# pong.net
KiCad netlist of a schematic drawn in EAGLE
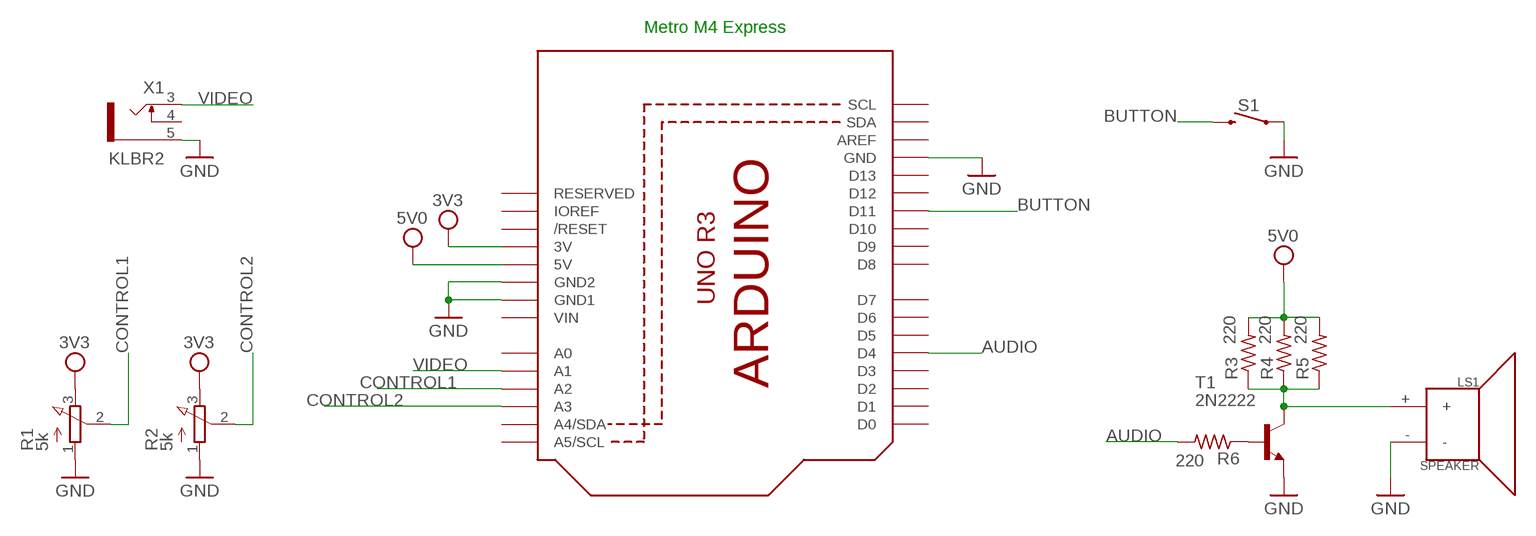
[diagram p0: schematic, sheet 1]

(export (version "E")
  (design (tool "Eeschema 10.0.6"))
  (components
    (comp (ref "LS1")
      (value "SPEAKER")
      (footprint "eagle-import:PCB_MOUNT_SPEAKER")
      (fields (field (name "SPICEPREFIX") "L"))
      (libsource (lib "eagle-import") (part "SPEAKER"))
    )
    (comp (ref "R1")
      (value "5k")
      (footprint "eagle-import:3RP_1610N")
      (libsource (lib "eagle-import") (part "3RP/1610N"))
    )
    (comp (ref "R2")
      (value "5k")
      (footprint "eagle-import:3RP_1610N")
      (libsource (lib "eagle-import") (part "3RP/1610N"))
    )
    (comp (ref "R3")
      (value "220")
      (footprint "eagle-import:0309_12")
      (fields (field (name "SPICEPREFIX") "R"))
      (libsource (lib "eagle-import") (part "R-US_0309/12"))
    )
    (comp (ref "R4")
      (value "220")
      (footprint "eagle-import:0309_12")
      (fields (field (name "SPICEPREFIX") "R"))
      (libsource (lib "eagle-import") (part "R-US_0309/12"))
    )
    (comp (ref "R5")
      (value "220")
      (footprint "eagle-import:0309_12")
      (fields (field (name "SPICEPREFIX") "R"))
      (libsource (lib "eagle-import") (part "R-US_0309/12"))
    )
    (comp (ref "R6")
      (value "220")
      (footprint "eagle-import:0309_12")
      (fields (field (name "SPICEPREFIX") "R"))
      (libsource (lib "eagle-import") (part "R-US_0309/12"))
    )
    (comp (ref "S1")
      (value "Start Button")
      (footprint "eagle-import:TACTILE_SWITCH_PTH_6.0MM_KIT")
      (libsource (lib "eagle-import") (part "MOMENTARY-SWITCH-SPST-PTH-6.0MM-KIT"))
    )
    (comp (ref "T1")
      (value "2N2222")
      (footprint "eagle-import:TO92-EBC-OVAL")
      (fields (field (name "SPICEPREFIX") "J"))
      (libsource (lib "eagle-import") (part "2N2222"))
    )
    (comp (ref "U1")
      (value "ARDUINOR3-DIMENSION")
      (footprint "eagle-import:ARDUINOR3")
      (libsource (lib "eagle-import") (part "ARDUINOR3-DIMENSION"))
    )
    (comp (ref "X1")
      (value "KLBR2")
      (footprint "eagle-import:KLBR2")
      (libsource (lib "eagle-import") (part "KLBR?2"))
    )
  )
  (nets
    (net (code "1") (name "/AUDIO") (class "Default")
      (node (ref "R6") (pin "2") (pinfunction "2_2") (pintype "passive"))
      (node (ref "U1") (pin "D4") (pinfunction "D4_D4") (pintype "bidirectional"))
    )
    (net (code "2") (name "/BUTTON") (class "Default")
      (node (ref "S1") (pin "3") (pinfunction "2_3") (pintype "passive"))
      (node (ref "U1") (pin "D11") (pinfunction "D11_D11") (pintype "bidirectional"))
    )
    (net (code "3") (name "/CONTROL1") (class "Default")
      (node (ref "R1") (pin "2") (pinfunction "S_2") (pintype "passive"))
      (node (ref "U1") (pin "A2") (pinfunction "A2_A2") (pintype "bidirectional"))
    )
    (net (code "4") (name "/CONTROL2") (class "Default")
      (node (ref "R2") (pin "2") (pinfunction "S_2") (pintype "passive"))
      (node (ref "U1") (pin "A3") (pinfunction "A3_A3") (pintype "bidirectional"))
    )
    (net (code "5") (name "/VIDEO") (class "Default")
      (node (ref "U1") (pin "A1") (pinfunction "A1_A1") (pintype "bidirectional"))
      (node (ref "X1") (pin "3") (pinfunction "3_3") (pintype "passive"))
    )
    (net (code "6") (name "/VIN") (class "Default")
      (node (ref "U1") (pin "VIN") (pinfunction "VIN_VIN") (pintype "power_in"))
    )
    (net (code "7") (name "3V3") (class "Default")
      (node (ref "R1") (pin "3") (pinfunction "E_3") (pintype "passive"))
      (node (ref "R2") (pin "3") (pinfunction "E_3") (pintype "passive"))
      (node (ref "U1") (pin "3V") (pinfunction "3V_3V") (pintype "power_in"))
    )
    (net (code "8") (name "5V0") (class "Default")
      (node (ref "R3") (pin "2") (pinfunction "2_2") (pintype "passive"))
      (node (ref "R4") (pin "2") (pinfunction "2_2") (pintype "passive"))
      (node (ref "R5") (pin "2") (pinfunction "2_2") (pintype "passive"))
      (node (ref "U1") (pin "5V") (pinfunction "5V_5V") (pintype "power_in"))
    )
    (net (code "9") (name "GND") (class "Default")
      (node (ref "LS1") (pin "-") (pinfunction "-_-") (pintype "bidirectional"))
      (node (ref "R1") (pin "1") (pinfunction "A_1") (pintype "passive"))
      (node (ref "R2") (pin "1") (pinfunction "A_1") (pintype "passive"))
      (node (ref "S1") (pin "1") (pinfunction "1_1") (pintype "passive"))
      (node (ref "T1") (pin "E") (pinfunction "E_E") (pintype "passive"))
      (node (ref "U1") (pin "GND") (pinfunction "GND_GND") (pintype "power_in"))
      (node (ref "U1") (pin "GND1") (pinfunction "GND1_GND1") (pintype "power_in"))
      (node (ref "U1") (pin "GND2") (pinfunction "GND2_GND2") (pintype "power_in"))
      (node (ref "X1") (pin "5") (pinfunction "5_5") (pintype "passive"))
    )
    (net (code "10") (name "Net-(LS1-Pad+)") (class "Default")
      (node (ref "LS1") (pin "+") (pinfunction "+_+") (pintype "bidirectional"))
      (node (ref "R3") (pin "1") (pinfunction "1_1") (pintype "passive"))
      (node (ref "R4") (pin "1") (pinfunction "1_1") (pintype "passive"))
      (node (ref "R5") (pin "1") (pinfunction "1_1") (pintype "passive"))
      (node (ref "T1") (pin "C") (pinfunction "C_C") (pintype "passive"))
    )
    (net (code "11") (name "Net-(R6-Pad1)") (class "Default")
      (node (ref "R6") (pin "1") (pinfunction "1_1") (pintype "passive"))
      (node (ref "T1") (pin "B") (pinfunction "B_B") (pintype "passive"))
    )
    (net (code "12") (name "unconnected-(U1-A4{slash}SDA-PadA4)") (class "Default")
      (node (ref "U1") (pin "A4") (pinfunction "A4/SDA_A4") (pintype "bidirectional"))
    )
    (net (code "13") (name "unconnected-(U1-A5{slash}SCL-PadA5)") (class "Default")
      (node (ref "U1") (pin "A5") (pinfunction "A5/SCL_A5") (pintype "bidirectional"))
    )
    (net (code "14") (name "unconnected-(U1-PadA0)") (class "Default")
      (node (ref "U1") (pin "A0") (pinfunction "A0_A0") (pintype "bidirectional"))
    )
    (net (code "15") (name "unconnected-(U1-PadAREF)") (class "Default")
      (node (ref "U1") (pin "AREF") (pinfunction "AREF_AREF") (pintype "bidirectional"))
    )
    (net (code "16") (name "unconnected-(U1-PadD0)") (class "Default")
      (node (ref "U1") (pin "D0") (pinfunction "D0_D0") (pintype "bidirectional"))
    )
    (net (code "17") (name "unconnected-(U1-PadD1)") (class "Default")
      (node (ref "U1") (pin "D1") (pinfunction "D1_D1") (pintype "bidirectional"))
    )
    (net (code "18") (name "unconnected-(U1-PadD2)") (class "Default")
      (node (ref "U1") (pin "D2") (pinfunction "D2_D2") (pintype "bidirectional"))
    )
    (net (code "19") (name "unconnected-(U1-PadD3)") (class "Default")
      (node (ref "U1") (pin "D3") (pinfunction "D3_D3") (pintype "bidirectional"))
    )
    (net (code "20") (name "unconnected-(U1-PadD5)") (class "Default")
      (node (ref "U1") (pin "D5") (pinfunction "D5_D5") (pintype "bidirectional"))
    )
    (net (code "21") (name "unconnected-(U1-PadD6)") (class "Default")
      (node (ref "U1") (pin "D6") (pinfunction "D6_D6") (pintype "bidirectional"))
    )
    (net (code "22") (name "unconnected-(U1-PadD7)") (class "Default")
      (node (ref "U1") (pin "D7") (pinfunction "D7_D7") (pintype "bidirectional"))
    )
    (net (code "23") (name "unconnected-(U1-PadD8)") (class "Default")
      (node (ref "U1") (pin "D8") (pinfunction "D8_D8") (pintype "bidirectional"))
    )
    (net (code "24") (name "unconnected-(U1-PadD9)") (class "Default")
      (node (ref "U1") (pin "D9") (pinfunction "D9_D9") (pintype "bidirectional"))
    )
    (net (code "25") (name "unconnected-(U1-PadD10)") (class "Default")
      (node (ref "U1") (pin "D10") (pinfunction "D10_D10") (pintype "bidirectional"))
    )
    (net (code "26") (name "unconnected-(U1-PadD12)") (class "Default")
      (node (ref "U1") (pin "D12") (pinfunction "D12_D12") (pintype "bidirectional"))
    )
    (net (code "27") (name "unconnected-(U1-PadD13)") (class "Default")
      (node (ref "U1") (pin "D13") (pinfunction "D13_D13") (pintype "bidirectional"))
    )
    (net (code "28") (name "unconnected-(U1-PadIOREF)") (class "Default")
      (node (ref "U1") (pin "IOREF") (pinfunction "IOREF_IOREF") (pintype "output"))
    )
    (net (code "29") (name "unconnected-(U1-PadRESERVED)") (class "Default")
      (node (ref "U1") (pin "RESERVED") (pinfunction "RESERVED_RESERVED") (pintype "no_connect"))
    )
    (net (code "30") (name "unconnected-(U1-PadSCL)") (class "Default")
      (node (ref "U1") (pin "SCL") (pinfunction "SCL_SCL") (pintype "bidirectional"))
    )
    (net (code "31") (name "unconnected-(U1-PadSDA)") (class "Default")
      (node (ref "U1") (pin "SDA") (pinfunction "SDA_SDA") (pintype "bidirectional"))
    )
    (net (code "32") (name "unconnected-(U1-{slash}RESET-PadRESET)") (class "Default")
      (node (ref "U1") (pin "RESET") (pinfunction "/RESET_RESET") (pintype "bidirectional"))
    )
    (net (code "33") (name "unconnected-(X1-Pad4)") (class "Default")
      (node (ref "X1") (pin "4") (pinfunction "4_4") (pintype "passive"))
    )
  )
)
